# ADC.net
KiCad netlist of a schematic drawn in Altium Designer
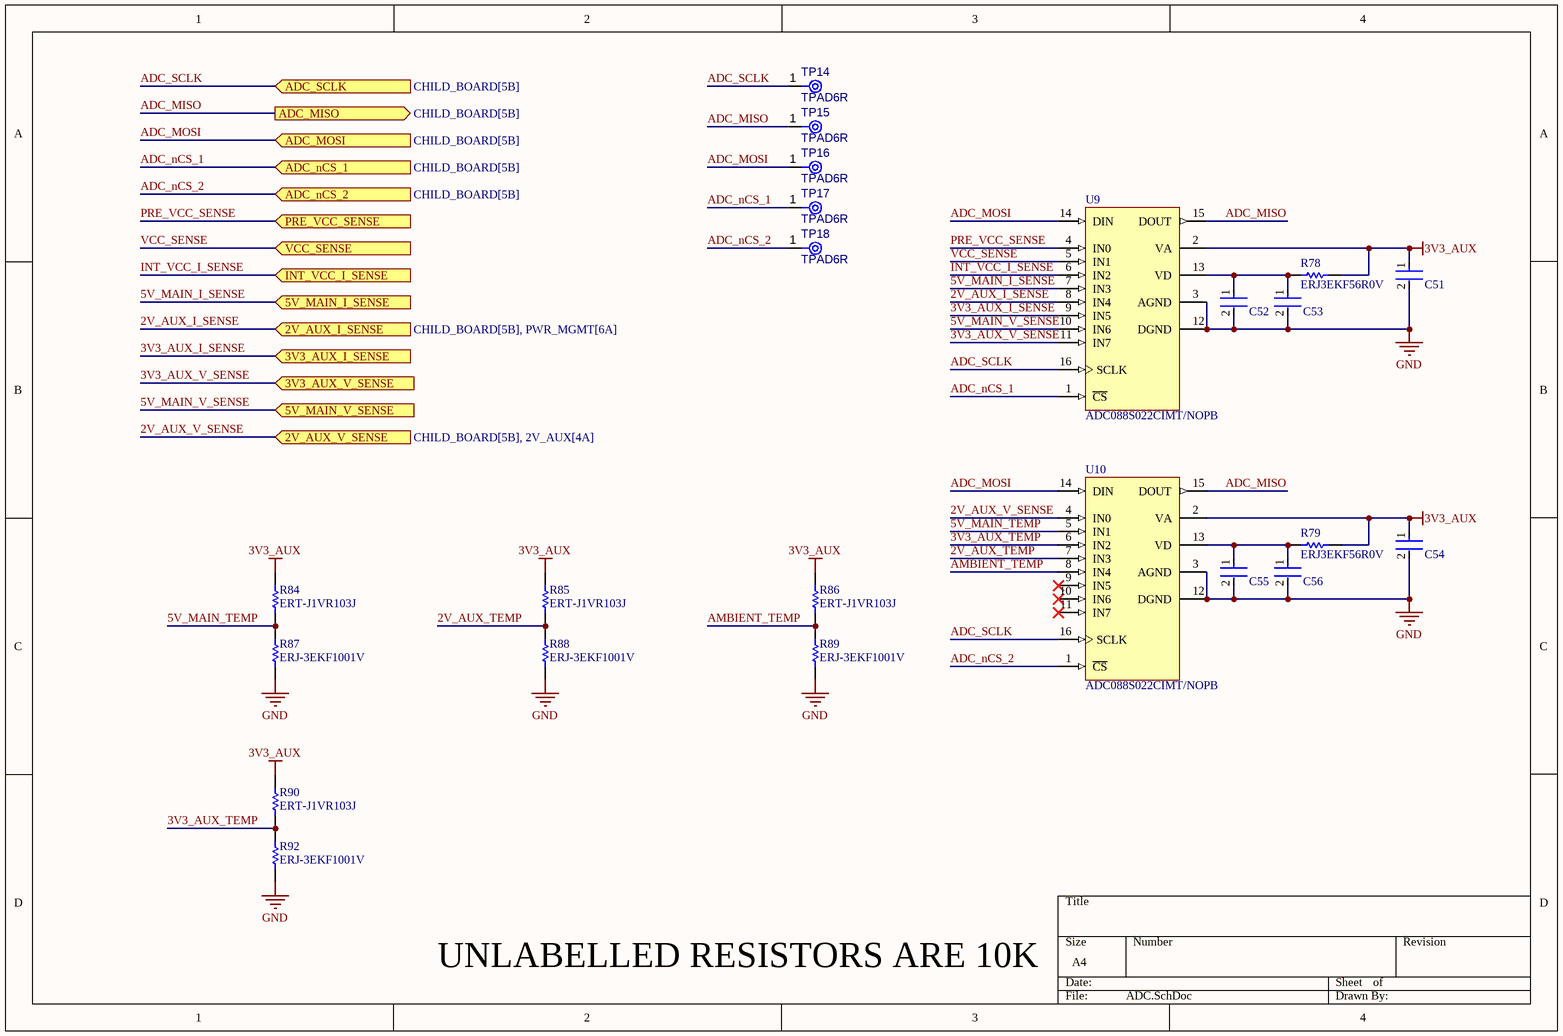
[diagram p0: ADC.SchDoc]

(export (version "E")
  (design (tool "Eeschema 10.0.6"))
  (components
    (comp (ref "C51")
      (value "C0402C104K8PACTU")
      (footprint "FP-C0402-BB-MFG")
      (description "CAP CER 0.1UF 10V X5R 0402")
      (fields (field (name "MANUFACTURER") "Kemet") (field (name "TOLERANCE") "0.1"))
      (libsource (lib "Altium Content Vault") (part "b4654b650e69147ec39a6b967a45e02"))
    )
    (comp (ref "C52")
      (value "C0402C104K8PACTU")
      (footprint "FP-C0402-BB-MFG")
      (description "CAP CER 0.1UF 10V X5R 0402")
      (fields (field (name "MANUFACTURER") "Kemet") (field (name "TOLERANCE") "0.1"))
      (libsource (lib "Altium Content Vault") (part "b4654b650e69147ec39a6b967a45e02"))
    )
    (comp (ref "C53")
      (value "C0402C104K8PACTU")
      (footprint "FP-C0402-BB-MFG")
      (description "CAP CER 0.1UF 10V X5R 0402")
      (fields (field (name "MANUFACTURER") "Kemet") (field (name "TOLERANCE") "0.1"))
      (libsource (lib "Altium Content Vault") (part "b4654b650e69147ec39a6b967a45e02"))
    )
    (comp (ref "C54")
      (value "C0402C104K8PACTU")
      (footprint "FP-C0402-BB-MFG")
      (description "CAP CER 0.1UF 10V X5R 0402")
      (fields (field (name "MANUFACTURER") "Kemet") (field (name "TOLERANCE") "0.1"))
      (libsource (lib "Altium Content Vault") (part "b4654b650e69147ec39a6b967a45e02"))
    )
    (comp (ref "C55")
      (value "C0402C104K8PACTU")
      (footprint "FP-C0402-BB-MFG")
      (description "CAP CER 0.1UF 10V X5R 0402")
      (fields (field (name "MANUFACTURER") "Kemet") (field (name "TOLERANCE") "0.1"))
      (libsource (lib "Altium Content Vault") (part "b4654b650e69147ec39a6b967a45e02"))
    )
    (comp (ref "C56")
      (value "C0402C104K8PACTU")
      (footprint "FP-C0402-BB-MFG")
      (description "CAP CER 0.1UF 10V X5R 0402")
      (fields (field (name "MANUFACTURER") "Kemet") (field (name "TOLERANCE") "0.1"))
      (libsource (lib "Altium Content Vault") (part "b4654b650e69147ec39a6b967a45e02"))
    )
    (comp (ref "R78")
      (value "ERJ3EKF56R0V")
      (footprint "RESC1608X55X30NL15T15")
      (fields (field (name "MANUFACTURER") "Panasonic"))
      (libsource (lib "Altium Content Vault") (part "RES"))
    )
    (comp (ref "R79")
      (value "ERJ3EKF56R0V")
      (footprint "RESC1608X55X30NL15T15")
      (fields (field (name "MANUFACTURER") "Panasonic"))
      (libsource (lib "Altium Content Vault") (part "RES"))
    )
    (comp (ref "R84")
      (value "ERT-J1VR103J")
      (footprint "RESC1608X90X30ML15T20")
      (fields (field (name "MANUFACTURER") "Panasonic"))
      (libsource (lib "Altium Content Vault") (part "RES"))
    )
    (comp (ref "R85")
      (value "ERT-J1VR103J")
      (footprint "RESC1608X90X30ML15T20")
      (fields (field (name "MANUFACTURER") "Panasonic"))
      (libsource (lib "Altium Content Vault") (part "RES"))
    )
    (comp (ref "R86")
      (value "ERT-J1VR103J")
      (footprint "RESC1608X90X30ML15T20")
      (fields (field (name "MANUFACTURER") "Panasonic"))
      (libsource (lib "Altium Content Vault") (part "RES"))
    )
    (comp (ref "R87")
      (value "ERJ-3EKF1001V")
      (footprint "RESC1608X55X30LL15T15")
      (fields (field (name "MANUFACTURER") "Panasonic"))
      (libsource (lib "Altium Content Vault") (part "RES"))
    )
    (comp (ref "R88")
      (value "ERJ-3EKF1001V")
      (footprint "RESC1608X55X30LL15T15")
      (fields (field (name "MANUFACTURER") "Panasonic"))
      (libsource (lib "Altium Content Vault") (part "RES"))
    )
    (comp (ref "R89")
      (value "ERJ-3EKF1001V")
      (footprint "RESC1608X55X30LL15T15")
      (fields (field (name "MANUFACTURER") "Panasonic"))
      (libsource (lib "Altium Content Vault") (part "RES"))
    )
    (comp (ref "R90")
      (value "ERT-J1VR103J")
      (footprint "RESC1608X90X30ML15T20")
      (fields (field (name "MANUFACTURER") "Panasonic"))
      (libsource (lib "Altium Content Vault") (part "RES"))
    )
    (comp (ref "R92")
      (value "ERJ-3EKF1001V")
      (footprint "RESC1608X55X30LL15T15")
      (fields (field (name "MANUFACTURER") "Panasonic"))
      (libsource (lib "Altium Content Vault") (part "RES"))
    )
    (comp (ref "TP14")
      (value "TPAD6R")
      (footprint "TP06R")
      (description "0.6mm round")
      (libsource (lib "uORocketry Hardware") (part "CMP-001-0001-4"))
    )
    (comp (ref "TP15")
      (value "TPAD6R")
      (footprint "TP06R")
      (description "0.6mm round")
      (libsource (lib "uORocketry Hardware") (part "CMP-001-0001-4"))
    )
    (comp (ref "TP16")
      (value "TPAD6R")
      (footprint "TP06R")
      (description "0.6mm round")
      (libsource (lib "uORocketry Hardware") (part "CMP-001-0001-4"))
    )
    (comp (ref "TP17")
      (value "TPAD6R")
      (footprint "TP06R")
      (description "0.6mm round")
      (libsource (lib "uORocketry Hardware") (part "CMP-001-0001-4"))
    )
    (comp (ref "TP18")
      (value "TPAD6R")
      (footprint "TP06R")
      (description "0.6mm round")
      (libsource (lib "uORocketry Hardware") (part "CMP-001-0001-4"))
    )
    (comp (ref "U9")
      (value "ADC088S022CIMT/NOPB")
      (footprint "MTC16_L")
      (description "8-Channel, 50 kSPS to 200 kSPS, 8-Bit A/D Converter, 16-pin TSSOP, Pb-Free")
      (fields (field (name "MANUFACTURER") "National Semiconductor"))
      (libsource (lib "Altium Content Vault") (part "CON-ADC-ADC108S052CIMT"))
    )
    (comp (ref "U10")
      (value "ADC088S022CIMT/NOPB")
      (footprint "MTC16_L")
      (description "8-Channel, 50 kSPS to 200 kSPS, 8-Bit A/D Converter, 16-pin TSSOP, Pb-Free")
      (fields (field (name "MANUFACTURER") "National Semiconductor"))
      (libsource (lib "Altium Content Vault") (part "CON-ADC-ADC108S052CIMT"))
    )
  )
  (nets
    (net (code "1") (name "/2V_AUX_I_SENSE") (class "Default")
      (node (ref "U9") (pin "8") (pinfunction "IN4_8") (pintype "input"))
    )
    (net (code "2") (name "/2V_AUX_TEMP") (class "Default")
      (node (ref "R85") (pin "1") (pinfunction "1_1") (pintype "passive"))
      (node (ref "R88") (pin "2") (pinfunction "2_2") (pintype "passive"))
      (node (ref "U10") (pin "7") (pinfunction "IN3_7") (pintype "input"))
    )
    (net (code "3") (name "/2V_AUX_V_SENSE") (class "Default")
      (node (ref "U10") (pin "4") (pinfunction "IN0_4") (pintype "input"))
    )
    (net (code "4") (name "/3V3_AUX_I_SENSE") (class "Default")
      (node (ref "U9") (pin "9") (pinfunction "IN5_9") (pintype "input"))
    )
    (net (code "5") (name "/3V3_AUX_TEMP") (class "Default")
      (node (ref "R90") (pin "1") (pinfunction "1_1") (pintype "passive"))
      (node (ref "R92") (pin "2") (pinfunction "2_2") (pintype "passive"))
      (node (ref "U10") (pin "6") (pinfunction "IN2_6") (pintype "input"))
    )
    (net (code "6") (name "/3V3_AUX_V_SENSE") (class "Default")
      (node (ref "U9") (pin "11") (pinfunction "IN7_11") (pintype "input"))
    )
    (net (code "7") (name "/5V_MAIN_I_SENSE") (class "Default")
      (node (ref "U9") (pin "7") (pinfunction "IN3_7") (pintype "input"))
    )
    (net (code "8") (name "/5V_MAIN_TEMP") (class "Default")
      (node (ref "R84") (pin "1") (pinfunction "1_1") (pintype "passive"))
      (node (ref "R87") (pin "2") (pinfunction "2_2") (pintype "passive"))
      (node (ref "U10") (pin "5") (pinfunction "IN1_5") (pintype "input"))
    )
    (net (code "9") (name "/5V_MAIN_V_SENSE") (class "Default")
      (node (ref "U9") (pin "10") (pinfunction "IN6_10") (pintype "input"))
    )
    (net (code "10") (name "/ADC_MISO") (class "Default")
      (node (ref "TP15") (pin "1") (pinfunction "TP_1") (pintype "passive"))
      (node (ref "U10") (pin "15") (pinfunction "DOUT_15") (pintype "output"))
      (node (ref "U9") (pin "15") (pinfunction "DOUT_15") (pintype "output"))
    )
    (net (code "11") (name "/ADC_MOSI") (class "Default")
      (node (ref "TP16") (pin "1") (pinfunction "TP_1") (pintype "passive"))
      (node (ref "U10") (pin "14") (pinfunction "DIN_14") (pintype "input"))
      (node (ref "U9") (pin "14") (pinfunction "DIN_14") (pintype "input"))
    )
    (net (code "12") (name "/ADC_SCLK") (class "Default")
      (node (ref "TP14") (pin "1") (pinfunction "TP_1") (pintype "passive"))
      (node (ref "U10") (pin "16") (pinfunction "SCLK_16") (pintype "input"))
      (node (ref "U9") (pin "16") (pinfunction "SCLK_16") (pintype "input"))
    )
    (net (code "13") (name "/ADC_nCS_1") (class "Default")
      (node (ref "TP17") (pin "1") (pinfunction "TP_1") (pintype "passive"))
      (node (ref "U9") (pin "1") (pinfunction "~{CS}_1") (pintype "input"))
    )
    (net (code "14") (name "/ADC_nCS_2") (class "Default")
      (node (ref "TP18") (pin "1") (pinfunction "TP_1") (pintype "passive"))
      (node (ref "U10") (pin "1") (pinfunction "~{CS}_1") (pintype "input"))
    )
    (net (code "15") (name "/AMBIENT_TEMP") (class "Default")
      (node (ref "R86") (pin "1") (pinfunction "1_1") (pintype "passive"))
      (node (ref "R89") (pin "2") (pinfunction "2_2") (pintype "passive"))
      (node (ref "U10") (pin "8") (pinfunction "IN4_8") (pintype "input"))
    )
    (net (code "16") (name "/INT_VCC_I_SENSE") (class "Default")
      (node (ref "U9") (pin "6") (pinfunction "IN2_6") (pintype "input"))
    )
    (net (code "17") (name "/PRE_VCC_SENSE") (class "Default")
      (node (ref "U9") (pin "4") (pinfunction "IN0_4") (pintype "input"))
    )
    (net (code "18") (name "/VCC_SENSE") (class "Default")
      (node (ref "U9") (pin "5") (pinfunction "IN1_5") (pintype "input"))
    )
    (net (code "19") (name "3V3_AUX") (class "Default")
      (node (ref "C51") (pin "1") (pinfunction "1_1") (pintype "passive"))
      (node (ref "C54") (pin "1") (pinfunction "1_1") (pintype "passive"))
      (node (ref "R78") (pin "1") (pinfunction "1_1") (pintype "passive"))
      (node (ref "R79") (pin "1") (pinfunction "1_1") (pintype "passive"))
      (node (ref "R84") (pin "2") (pinfunction "2_2") (pintype "passive"))
      (node (ref "R85") (pin "2") (pinfunction "2_2") (pintype "passive"))
      (node (ref "R86") (pin "2") (pinfunction "2_2") (pintype "passive"))
      (node (ref "R90") (pin "2") (pinfunction "2_2") (pintype "passive"))
      (node (ref "U10") (pin "2") (pinfunction "VA_2") (pintype "power_in"))
      (node (ref "U9") (pin "2") (pinfunction "VA_2") (pintype "power_in"))
    )
    (net (code "20") (name "GND") (class "Default")
      (node (ref "C51") (pin "2") (pinfunction "2_2") (pintype "passive"))
      (node (ref "C52") (pin "2") (pinfunction "2_2") (pintype "passive"))
      (node (ref "C53") (pin "2") (pinfunction "2_2") (pintype "passive"))
      (node (ref "C54") (pin "2") (pinfunction "2_2") (pintype "passive"))
      (node (ref "C55") (pin "2") (pinfunction "2_2") (pintype "passive"))
      (node (ref "C56") (pin "2") (pinfunction "2_2") (pintype "passive"))
      (node (ref "R87") (pin "1") (pinfunction "1_1") (pintype "passive"))
      (node (ref "R88") (pin "1") (pinfunction "1_1") (pintype "passive"))
      (node (ref "R89") (pin "1") (pinfunction "1_1") (pintype "passive"))
      (node (ref "R92") (pin "1") (pinfunction "1_1") (pintype "passive"))
      (node (ref "U10") (pin "12") (pinfunction "DGND_12") (pintype "power_in"))
      (node (ref "U10") (pin "3") (pinfunction "AGND_3") (pintype "power_in"))
      (node (ref "U9") (pin "12") (pinfunction "DGND_12") (pintype "power_in"))
      (node (ref "U9") (pin "3") (pinfunction "AGND_3") (pintype "power_in"))
    )
    (net (code "21") (name "Net-(U9-VD)") (class "Default")
      (node (ref "C52") (pin "1") (pinfunction "1_1") (pintype "passive"))
      (node (ref "C53") (pin "1") (pinfunction "1_1") (pintype "passive"))
      (node (ref "R78") (pin "2") (pinfunction "2_2") (pintype "passive"))
      (node (ref "U9") (pin "13") (pinfunction "VD_13") (pintype "power_in"))
    )
    (net (code "22") (name "Net-(U10-VD)") (class "Default")
      (node (ref "C55") (pin "1") (pinfunction "1_1") (pintype "passive"))
      (node (ref "C56") (pin "1") (pinfunction "1_1") (pintype "passive"))
      (node (ref "R79") (pin "2") (pinfunction "2_2") (pintype "passive"))
      (node (ref "U10") (pin "13") (pinfunction "VD_13") (pintype "power_in"))
    )
    (net (code "23") (name "unconnected-(U10-IN5-Pad9)") (class "Default")
      (node (ref "U10") (pin "9") (pinfunction "IN5_9") (pintype "input+no_connect"))
    )
    (net (code "24") (name "unconnected-(U10-IN6-Pad10)") (class "Default")
      (node (ref "U10") (pin "10") (pinfunction "IN6_10") (pintype "input+no_connect"))
    )
    (net (code "25") (name "unconnected-(U10-IN7-Pad11)") (class "Default")
      (node (ref "U10") (pin "11") (pinfunction "IN7_11") (pintype "input+no_connect"))
    )
  )
)
